# 2k6-0005.net
KiCad netlist of a schematic drawn in EAGLE
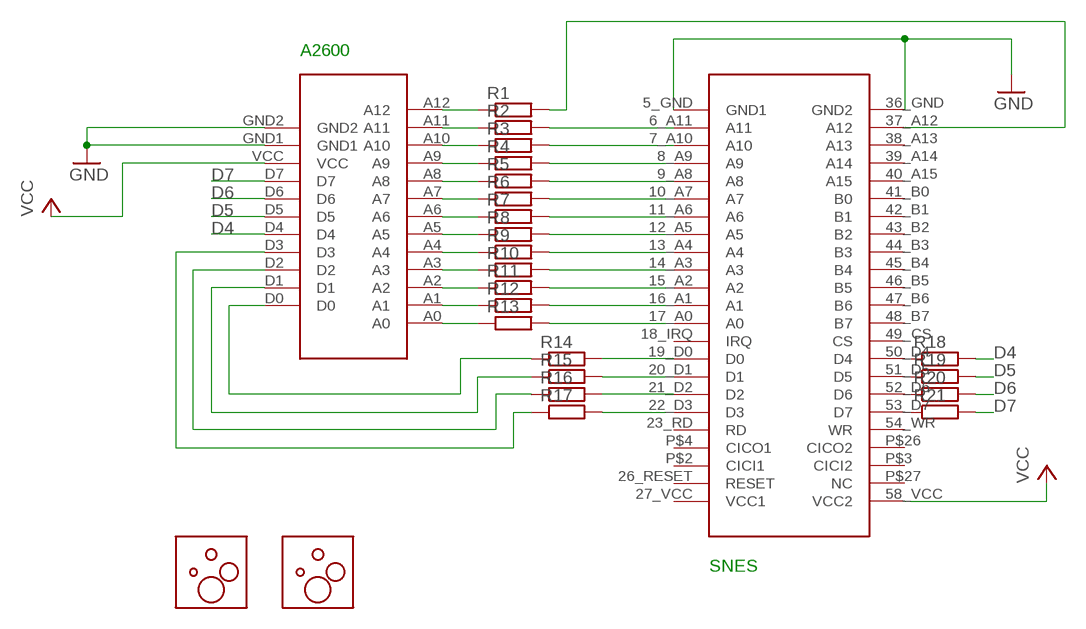
[diagram p0: schematic, sheet 1]

(export (version "E")
  (design (tool "Eeschema 10.0.6"))
  (components
    (comp (ref "R1")
      (value "R-EU_R0402")
      (footprint "eagle-import:R0402")
      (libsource (lib "eagle-import") (part "R-EU_R0402"))
    )
    (comp (ref "R2")
      (value "R-EU_R0402")
      (footprint "eagle-import:R0402")
      (libsource (lib "eagle-import") (part "R-EU_R0402"))
    )
    (comp (ref "R3")
      (value "R-EU_R0402")
      (footprint "eagle-import:R0402")
      (libsource (lib "eagle-import") (part "R-EU_R0402"))
    )
    (comp (ref "R4")
      (value "R-EU_R0402")
      (footprint "eagle-import:R0402")
      (libsource (lib "eagle-import") (part "R-EU_R0402"))
    )
    (comp (ref "R5")
      (value "R-EU_R0402")
      (footprint "eagle-import:R0402")
      (libsource (lib "eagle-import") (part "R-EU_R0402"))
    )
    (comp (ref "R6")
      (value "R-EU_R0402")
      (footprint "eagle-import:R0402")
      (libsource (lib "eagle-import") (part "R-EU_R0402"))
    )
    (comp (ref "R7")
      (value "R-EU_R0402")
      (footprint "eagle-import:R0402")
      (libsource (lib "eagle-import") (part "R-EU_R0402"))
    )
    (comp (ref "R8")
      (value "R-EU_R0402")
      (footprint "eagle-import:R0402")
      (libsource (lib "eagle-import") (part "R-EU_R0402"))
    )
    (comp (ref "R9")
      (value "R-EU_R0402")
      (footprint "eagle-import:R0402")
      (libsource (lib "eagle-import") (part "R-EU_R0402"))
    )
    (comp (ref "R10")
      (value "R-EU_R0402")
      (footprint "eagle-import:R0402")
      (libsource (lib "eagle-import") (part "R-EU_R0402"))
    )
    (comp (ref "R11")
      (value "R-EU_R0402")
      (footprint "eagle-import:R0402")
      (libsource (lib "eagle-import") (part "R-EU_R0402"))
    )
    (comp (ref "R12")
      (value "R-EU_R0402")
      (footprint "eagle-import:R0402")
      (libsource (lib "eagle-import") (part "R-EU_R0402"))
    )
    (comp (ref "R13")
      (value "R-EU_R0402")
      (footprint "eagle-import:R0402")
      (libsource (lib "eagle-import") (part "R-EU_R0402"))
    )
    (comp (ref "R14")
      (value "R-EU_R0402")
      (footprint "eagle-import:R0402")
      (libsource (lib "eagle-import") (part "R-EU_R0402"))
    )
    (comp (ref "R15")
      (value "R-EU_R0402")
      (footprint "eagle-import:R0402")
      (libsource (lib "eagle-import") (part "R-EU_R0402"))
    )
    (comp (ref "R16")
      (value "R-EU_R0402")
      (footprint "eagle-import:R0402")
      (libsource (lib "eagle-import") (part "R-EU_R0402"))
    )
    (comp (ref "R17")
      (value "R-EU_R0402")
      (footprint "eagle-import:R0402")
      (libsource (lib "eagle-import") (part "R-EU_R0402"))
    )
    (comp (ref "R18")
      (value "R-EU_R0402")
      (footprint "eagle-import:R0402")
      (libsource (lib "eagle-import") (part "R-EU_R0402"))
    )
    (comp (ref "R19")
      (value "R-EU_R0402")
      (footprint "eagle-import:R0402")
      (libsource (lib "eagle-import") (part "R-EU_R0402"))
    )
    (comp (ref "R20")
      (value "R-EU_R0402")
      (footprint "eagle-import:R0402")
      (libsource (lib "eagle-import") (part "R-EU_R0402"))
    )
    (comp (ref "R21")
      (value "R-EU_R0402")
      (footprint "eagle-import:R0402")
      (libsource (lib "eagle-import") (part "R-EU_R0402"))
    )
    (comp (ref "U$1")
      (value "2600CARTBIGGERPADS")
      (footprint "eagle-import:2600EDGE-BIGGER")
      (libsource (lib "eagle-import") (part "2600CARTBIGGERPADS"))
    )
    (comp (ref "U$2")
      (value "SNESCART")
      (footprint "eagle-import:SNESEDGE")
      (libsource (lib "eagle-import") (part "SNESCART"))
    )
    (comp (ref "U$3")
      (value "STENCIL-ALIGN")
      (footprint "eagle-import:STENCIL-ALIGN")
      (libsource (lib "eagle-import") (part "STENCIL-ALIGN"))
    )
    (comp (ref "U$4")
      (value "STENCIL-ALIGN")
      (footprint "eagle-import:STENCIL-ALIGN")
      (libsource (lib "eagle-import") (part "STENCIL-ALIGN"))
    )
  )
  (nets
    (net (code "1") (name "/D4") (class "Default")
      (node (ref "R18") (pin "2") (pinfunction "2_2") (pintype "passive"))
      (node (ref "U$1") (pin "D4") (pinfunction "D4_D4") (pintype "bidirectional"))
    )
    (net (code "2") (name "/D5") (class "Default")
      (node (ref "R19") (pin "2") (pinfunction "2_2") (pintype "passive"))
      (node (ref "U$1") (pin "D5") (pinfunction "D5_D5") (pintype "bidirectional"))
    )
    (net (code "3") (name "/D6") (class "Default")
      (node (ref "R20") (pin "2") (pinfunction "2_2") (pintype "passive"))
      (node (ref "U$1") (pin "D6") (pinfunction "D6_D6") (pintype "bidirectional"))
    )
    (net (code "4") (name "/D7") (class "Default")
      (node (ref "R21") (pin "2") (pinfunction "2_2") (pintype "passive"))
      (node (ref "U$1") (pin "D7") (pinfunction "D7_D7") (pintype "bidirectional"))
    )
    (net (code "5") (name "GND") (class "Default")
      (node (ref "U$1") (pin "GND1") (pinfunction "GND1_GND1") (pintype "bidirectional"))
      (node (ref "U$1") (pin "GND2") (pinfunction "GND2_GND2") (pintype "bidirectional"))
      (node (ref "U$2") (pin "36_GND") (pinfunction "GND2_36_GND") (pintype "bidirectional"))
      (node (ref "U$2") (pin "5_GND") (pinfunction "GND1_5_GND") (pintype "bidirectional"))
    )
    (net (code "6") (name "Net-(R1-Pad1)") (class "Default")
      (node (ref "R1") (pin "1") (pinfunction "1_1") (pintype "passive"))
      (node (ref "U$1") (pin "A12") (pinfunction "A12_A12") (pintype "bidirectional"))
    )
    (net (code "7") (name "Net-(R2-Pad1)") (class "Default")
      (node (ref "R2") (pin "1") (pinfunction "1_1") (pintype "passive"))
      (node (ref "U$1") (pin "A11") (pinfunction "A11_A11") (pintype "bidirectional"))
    )
    (net (code "8") (name "Net-(R3-Pad1)") (class "Default")
      (node (ref "R3") (pin "1") (pinfunction "1_1") (pintype "passive"))
      (node (ref "U$1") (pin "A10") (pinfunction "A10_A10") (pintype "bidirectional"))
    )
    (net (code "9") (name "Net-(R4-Pad1)") (class "Default")
      (node (ref "R4") (pin "1") (pinfunction "1_1") (pintype "passive"))
      (node (ref "U$1") (pin "A9") (pinfunction "A9_A9") (pintype "bidirectional"))
    )
    (net (code "10") (name "Net-(R5-Pad1)") (class "Default")
      (node (ref "R5") (pin "1") (pinfunction "1_1") (pintype "passive"))
      (node (ref "U$1") (pin "A8") (pinfunction "A8_A8") (pintype "bidirectional"))
    )
    (net (code "11") (name "Net-(R6-Pad1)") (class "Default")
      (node (ref "R6") (pin "1") (pinfunction "1_1") (pintype "passive"))
      (node (ref "U$1") (pin "A7") (pinfunction "A7_A7") (pintype "bidirectional"))
    )
    (net (code "12") (name "Net-(R7-Pad1)") (class "Default")
      (node (ref "R7") (pin "1") (pinfunction "1_1") (pintype "passive"))
      (node (ref "U$1") (pin "A6") (pinfunction "A6_A6") (pintype "bidirectional"))
    )
    (net (code "13") (name "Net-(R8-Pad1)") (class "Default")
      (node (ref "R8") (pin "1") (pinfunction "1_1") (pintype "passive"))
      (node (ref "U$1") (pin "A5") (pinfunction "A5_A5") (pintype "bidirectional"))
    )
    (net (code "14") (name "Net-(R9-Pad1)") (class "Default")
      (node (ref "R9") (pin "1") (pinfunction "1_1") (pintype "passive"))
      (node (ref "U$1") (pin "A4") (pinfunction "A4_A4") (pintype "bidirectional"))
    )
    (net (code "15") (name "Net-(R10-Pad1)") (class "Default")
      (node (ref "R10") (pin "1") (pinfunction "1_1") (pintype "passive"))
      (node (ref "U$1") (pin "A3") (pinfunction "A3_A3") (pintype "bidirectional"))
    )
    (net (code "16") (name "Net-(R11-Pad1)") (class "Default")
      (node (ref "R11") (pin "1") (pinfunction "1_1") (pintype "passive"))
      (node (ref "U$1") (pin "A2") (pinfunction "A2_A2") (pintype "bidirectional"))
    )
    (net (code "17") (name "Net-(R12-Pad1)") (class "Default")
      (node (ref "R12") (pin "1") (pinfunction "1_1") (pintype "passive"))
      (node (ref "U$1") (pin "A1") (pinfunction "A1_A1") (pintype "bidirectional"))
    )
    (net (code "18") (name "Net-(R13-Pad1)") (class "Default")
      (node (ref "R13") (pin "1") (pinfunction "1_1") (pintype "passive"))
      (node (ref "U$1") (pin "A0") (pinfunction "A0_A0") (pintype "bidirectional"))
    )
    (net (code "19") (name "Net-(R14-Pad1)") (class "Default")
      (node (ref "R14") (pin "1") (pinfunction "1_1") (pintype "passive"))
      (node (ref "U$1") (pin "D0") (pinfunction "D0_D0") (pintype "bidirectional"))
    )
    (net (code "20") (name "Net-(R15-Pad1)") (class "Default")
      (node (ref "R15") (pin "1") (pinfunction "1_1") (pintype "passive"))
      (node (ref "U$1") (pin "D1") (pinfunction "D1_D1") (pintype "bidirectional"))
    )
    (net (code "21") (name "Net-(R16-Pad1)") (class "Default")
      (node (ref "R16") (pin "1") (pinfunction "1_1") (pintype "passive"))
      (node (ref "U$1") (pin "D2") (pinfunction "D2_D2") (pintype "bidirectional"))
    )
    (net (code "22") (name "Net-(R17-Pad1)") (class "Default")
      (node (ref "R17") (pin "1") (pinfunction "1_1") (pintype "passive"))
      (node (ref "U$1") (pin "D3") (pinfunction "D3_D3") (pintype "bidirectional"))
    )
    (net (code "23") (name "Net-(U$2-A0)") (class "Default")
      (node (ref "R13") (pin "2") (pinfunction "2_2") (pintype "passive"))
      (node (ref "U$2") (pin "17_A0") (pinfunction "A0_17_A0") (pintype "bidirectional"))
    )
    (net (code "24") (name "Net-(U$2-A1)") (class "Default")
      (node (ref "R12") (pin "2") (pinfunction "2_2") (pintype "passive"))
      (node (ref "U$2") (pin "16_A1") (pinfunction "A1_16_A1") (pintype "bidirectional"))
    )
    (net (code "25") (name "Net-(U$2-A2)") (class "Default")
      (node (ref "R11") (pin "2") (pinfunction "2_2") (pintype "passive"))
      (node (ref "U$2") (pin "15_A2") (pinfunction "A2_15_A2") (pintype "bidirectional"))
    )
    (net (code "26") (name "Net-(U$2-A3)") (class "Default")
      (node (ref "R10") (pin "2") (pinfunction "2_2") (pintype "passive"))
      (node (ref "U$2") (pin "14_A3") (pinfunction "A3_14_A3") (pintype "bidirectional"))
    )
    (net (code "27") (name "Net-(U$2-A4)") (class "Default")
      (node (ref "R9") (pin "2") (pinfunction "2_2") (pintype "passive"))
      (node (ref "U$2") (pin "13_A4") (pinfunction "A4_13_A4") (pintype "bidirectional"))
    )
    (net (code "28") (name "Net-(U$2-A5)") (class "Default")
      (node (ref "R8") (pin "2") (pinfunction "2_2") (pintype "passive"))
      (node (ref "U$2") (pin "12_A5") (pinfunction "A5_12_A5") (pintype "bidirectional"))
    )
    (net (code "29") (name "Net-(U$2-A6)") (class "Default")
      (node (ref "R7") (pin "2") (pinfunction "2_2") (pintype "passive"))
      (node (ref "U$2") (pin "11_A6") (pinfunction "A6_11_A6") (pintype "bidirectional"))
    )
    (net (code "30") (name "Net-(U$2-A7)") (class "Default")
      (node (ref "R6") (pin "2") (pinfunction "2_2") (pintype "passive"))
      (node (ref "U$2") (pin "10_A7") (pinfunction "A7_10_A7") (pintype "bidirectional"))
    )
    (net (code "31") (name "Net-(U$2-A8)") (class "Default")
      (node (ref "R5") (pin "2") (pinfunction "2_2") (pintype "passive"))
      (node (ref "U$2") (pin "9_A8") (pinfunction "A8_9_A8") (pintype "bidirectional"))
    )
    (net (code "32") (name "Net-(U$2-A9)") (class "Default")
      (node (ref "R4") (pin "2") (pinfunction "2_2") (pintype "passive"))
      (node (ref "U$2") (pin "8_A9") (pinfunction "A9_8_A9") (pintype "bidirectional"))
    )
    (net (code "33") (name "Net-(U$2-A10)") (class "Default")
      (node (ref "R3") (pin "2") (pinfunction "2_2") (pintype "passive"))
      (node (ref "U$2") (pin "7_A10") (pinfunction "A10_7_A10") (pintype "bidirectional"))
    )
    (net (code "34") (name "Net-(U$2-A11)") (class "Default")
      (node (ref "R2") (pin "2") (pinfunction "2_2") (pintype "passive"))
      (node (ref "U$2") (pin "6_A11") (pinfunction "A11_6_A11") (pintype "bidirectional"))
    )
    (net (code "35") (name "Net-(U$2-A12)") (class "Default")
      (node (ref "R1") (pin "2") (pinfunction "2_2") (pintype "passive"))
      (node (ref "U$2") (pin "37_A12") (pinfunction "A12_37_A12") (pintype "bidirectional"))
    )
    (net (code "36") (name "Net-(U$2-D0)") (class "Default")
      (node (ref "R14") (pin "2") (pinfunction "2_2") (pintype "passive"))
      (node (ref "U$2") (pin "19_D0") (pinfunction "D0_19_D0") (pintype "bidirectional"))
    )
    (net (code "37") (name "Net-(U$2-D1)") (class "Default")
      (node (ref "R15") (pin "2") (pinfunction "2_2") (pintype "passive"))
      (node (ref "U$2") (pin "20_D1") (pinfunction "D1_20_D1") (pintype "bidirectional"))
    )
    (net (code "38") (name "Net-(U$2-D2)") (class "Default")
      (node (ref "R16") (pin "2") (pinfunction "2_2") (pintype "passive"))
      (node (ref "U$2") (pin "21_D2") (pinfunction "D2_21_D2") (pintype "bidirectional"))
    )
    (net (code "39") (name "Net-(U$2-D3)") (class "Default")
      (node (ref "R17") (pin "2") (pinfunction "2_2") (pintype "passive"))
      (node (ref "U$2") (pin "22_D3") (pinfunction "D3_22_D3") (pintype "bidirectional"))
    )
    (net (code "40") (name "Net-(U$2-D4)") (class "Default")
      (node (ref "R18") (pin "1") (pinfunction "1_1") (pintype "passive"))
      (node (ref "U$2") (pin "50_D4") (pinfunction "D4_50_D4") (pintype "bidirectional"))
    )
    (net (code "41") (name "Net-(U$2-D5)") (class "Default")
      (node (ref "R19") (pin "1") (pinfunction "1_1") (pintype "passive"))
      (node (ref "U$2") (pin "51_D5") (pinfunction "D5_51_D5") (pintype "bidirectional"))
    )
    (net (code "42") (name "Net-(U$2-D6)") (class "Default")
      (node (ref "R20") (pin "1") (pinfunction "1_1") (pintype "passive"))
      (node (ref "U$2") (pin "52_D6") (pinfunction "D6_52_D6") (pintype "bidirectional"))
    )
    (net (code "43") (name "Net-(U$2-D7)") (class "Default")
      (node (ref "R21") (pin "1") (pinfunction "1_1") (pintype "passive"))
      (node (ref "U$2") (pin "53_D7") (pinfunction "D7_53_D7") (pintype "bidirectional"))
    )
    (net (code "44") (name "VCC") (class "Default")
      (node (ref "U$1") (pin "VCC") (pinfunction "VCC_VCC") (pintype "bidirectional"))
      (node (ref "U$2") (pin "58_VCC") (pinfunction "VCC2_58_VCC") (pintype "bidirectional"))
    )
    (net (code "45") (name "unconnected-(U$2-A13-Pad38_A13)") (class "Default")
      (node (ref "U$2") (pin "38_A13") (pinfunction "A13_38_A13") (pintype "bidirectional"))
    )
    (net (code "46") (name "unconnected-(U$2-A14-Pad39_A14)") (class "Default")
      (node (ref "U$2") (pin "39_A14") (pinfunction "A14_39_A14") (pintype "bidirectional"))
    )
    (net (code "47") (name "unconnected-(U$2-A15-Pad40_A15)") (class "Default")
      (node (ref "U$2") (pin "40_A15") (pinfunction "A15_40_A15") (pintype "bidirectional"))
    )
    (net (code "48") (name "unconnected-(U$2-B0-Pad41_B0)") (class "Default")
      (node (ref "U$2") (pin "41_B0") (pinfunction "B0_41_B0") (pintype "bidirectional"))
    )
    (net (code "49") (name "unconnected-(U$2-B1-Pad42_B1)") (class "Default")
      (node (ref "U$2") (pin "42_B1") (pinfunction "B1_42_B1") (pintype "bidirectional"))
    )
    (net (code "50") (name "unconnected-(U$2-B2-Pad43_B2)") (class "Default")
      (node (ref "U$2") (pin "43_B2") (pinfunction "B2_43_B2") (pintype "bidirectional"))
    )
    (net (code "51") (name "unconnected-(U$2-B3-Pad44_B3)") (class "Default")
      (node (ref "U$2") (pin "44_B3") (pinfunction "B3_44_B3") (pintype "bidirectional"))
    )
    (net (code "52") (name "unconnected-(U$2-B4-Pad45_B4)") (class "Default")
      (node (ref "U$2") (pin "45_B4") (pinfunction "B4_45_B4") (pintype "bidirectional"))
    )
    (net (code "53") (name "unconnected-(U$2-B5-Pad46_B5)") (class "Default")
      (node (ref "U$2") (pin "46_B5") (pinfunction "B5_46_B5") (pintype "bidirectional"))
    )
    (net (code "54") (name "unconnected-(U$2-B6-Pad47_B6)") (class "Default")
      (node (ref "U$2") (pin "47_B6") (pinfunction "B6_47_B6") (pintype "bidirectional"))
    )
    (net (code "55") (name "unconnected-(U$2-B7-Pad48_B7)") (class "Default")
      (node (ref "U$2") (pin "48_B7") (pinfunction "B7_48_B7") (pintype "bidirectional"))
    )
    (net (code "56") (name "unconnected-(U$2-CICI1-PadP$2)") (class "Default")
      (node (ref "U$2") (pin "P$2") (pinfunction "CICI1_P$2") (pintype "bidirectional"))
    )
    (net (code "57") (name "unconnected-(U$2-CICI2-PadP$3)") (class "Default")
      (node (ref "U$2") (pin "P$3") (pinfunction "CICI2_P$3") (pintype "bidirectional"))
    )
    (net (code "58") (name "unconnected-(U$2-CICO1-PadP$4)") (class "Default")
      (node (ref "U$2") (pin "P$4") (pinfunction "CICO1_P$4") (pintype "bidirectional"))
    )
    (net (code "59") (name "unconnected-(U$2-CICO2-PadP$26)") (class "Default")
      (node (ref "U$2") (pin "P$26") (pinfunction "CICO2_P$26") (pintype "bidirectional"))
    )
    (net (code "60") (name "unconnected-(U$2-CS-Pad49_CS)") (class "Default")
      (node (ref "U$2") (pin "49_CS") (pinfunction "CS_49_CS") (pintype "bidirectional"))
    )
    (net (code "61") (name "unconnected-(U$2-IRQ-Pad18_IRQ)") (class "Default")
      (node (ref "U$2") (pin "18_IRQ") (pinfunction "IRQ_18_IRQ") (pintype "bidirectional"))
    )
    (net (code "62") (name "unconnected-(U$2-NC-PadP$27)") (class "Default")
      (node (ref "U$2") (pin "P$27") (pinfunction "NC_P$27") (pintype "bidirectional"))
    )
    (net (code "63") (name "unconnected-(U$2-RD-Pad23_RD)") (class "Default")
      (node (ref "U$2") (pin "23_RD") (pinfunction "RD_23_RD") (pintype "bidirectional"))
    )
    (net (code "64") (name "unconnected-(U$2-RESET-Pad26_RESET)") (class "Default")
      (node (ref "U$2") (pin "26_RESET") (pinfunction "RESET_26_RESET") (pintype "bidirectional"))
    )
    (net (code "65") (name "unconnected-(U$2-VCC1-Pad27_VCC)") (class "Default")
      (node (ref "U$2") (pin "27_VCC") (pinfunction "VCC1_27_VCC") (pintype "bidirectional"))
    )
    (net (code "66") (name "unconnected-(U$2-WR-Pad54_WR)") (class "Default")
      (node (ref "U$2") (pin "54_WR") (pinfunction "WR_54_WR") (pintype "bidirectional"))
    )
  )
)
